# Power-5V.net
KiCad netlist of a schematic drawn in Altium Designer
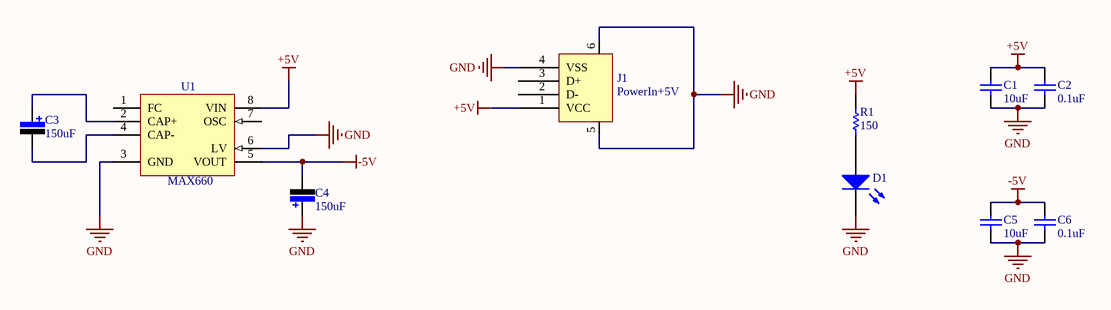
[diagram p0: Power-5V.SchDoc]

(export (version "E")
  (design (tool "Eeschema 10.0.6"))
  (components
    (comp (ref "C1")
      (value "10uF")
      (footprint "RB0.1/0.2")
      (description "无极性电容")
      (fields (field (name "Comment") "Cap") (field (name "PUBLISHER") "Altium Limited"))
      (libsource (lib "Fszhang") (part "Cap"))
    )
    (comp (ref "C2")
      (value "0.1uF")
      (footprint "C-RAD")
      (description "无极性电容")
      (fields (field (name "Comment") "Cap") (field (name "PUBLISHER") "Altium Limited"))
      (libsource (lib "Fszhang") (part "Cap"))
    )
    (comp (ref "C3")
      (value "150uF")
      (footprint "RB0.15/3")
      (description "极性电解电容")
      (fields (field (name "Comment") "Cap Pol") (field (name "PUBLISHER") "Altium Limited"))
      (libsource (lib "Fszhang") (part "Cap Pol"))
    )
    (comp (ref "C4")
      (value "150uF")
      (footprint "RB0.15/3")
      (description "极性电解电容")
      (fields (field (name "Comment") "Cap Pol") (field (name "PUBLISHER") "Altium Limited"))
      (libsource (lib "") (part "Cap Pol_1"))
    )
    (comp (ref "C5")
      (value "10uF")
      (footprint "RB0.1/0.2")
      (description "无极性电容")
      (fields (field (name "Comment") "Cap") (field (name "PUBLISHER") "Altium Limited"))
      (libsource (lib "Fszhang") (part "Cap"))
    )
    (comp (ref "C6")
      (value "0.1uF")
      (footprint "C-RAD")
      (description "无极性电容")
      (fields (field (name "Comment") "Cap") (field (name "PUBLISHER") "Altium Limited"))
      (libsource (lib "Fszhang") (part "Cap"))
    )
    (comp (ref "D1")
      (value "LED0")
      (footprint "RB2.54/4")
      (description "Typical INFRARED GaAs LED")
      (fields (field (name "PUBLISHER") "Altium Limited"))
      (libsource (lib "Miscellaneous Devices") (part "LED0"))
    )
    (comp (ref "J1")
      (value "PowerIn+5V")
      (footprint "USB_A1")
      (description "USB接口")
      (libsource (lib "Fszhang") (part "USB"))
    )
    (comp (ref "R1")
      (value "150")
      (footprint "AXIAL-0.3")
      (description "Resistor")
      (fields (field (name "Comment") "Res1") (field (name "PUBLISHER") "Altium Limited"))
      (libsource (lib "Miscellaneous Devices") (part "Res1"))
    )
    (comp (ref "U1")
      (value "MAX660")
      (footprint "DIP-8")
      (description "-5V电源芯片")
      (fields (field (name "PUBLISHER") "Altium Limited"))
      (libsource (lib "Fszhang") (part "MAX660CSA"))
    )
  )
  (nets
    (net (code "1") (name "+5V") (class "Default")
      (node (ref "C1") (pin "2") (pinfunction "2_2") (pintype "passive"))
      (node (ref "C2") (pin "2") (pinfunction "2_2") (pintype "passive"))
      (node (ref "J1") (pin "1") (pinfunction "VCC_1") (pintype "passive"))
      (node (ref "R1") (pin "2") (pinfunction "2_2") (pintype "passive"))
      (node (ref "U1") (pin "8") (pinfunction "VIN_8") (pintype "power_in"))
    )
    (net (code "2") (name "-5V") (class "Default")
      (node (ref "C4") (pin "2") (pinfunction "2_2") (pintype "passive"))
      (node (ref "C5") (pin "2") (pinfunction "2_2") (pintype "passive"))
      (node (ref "C6") (pin "2") (pinfunction "2_2") (pintype "passive"))
      (node (ref "U1") (pin "5") (pinfunction "VOUT_5") (pintype "power_in"))
    )
    (net (code "3") (name "GND") (class "Default")
      (node (ref "C1") (pin "1") (pinfunction "1_1") (pintype "passive"))
      (node (ref "C2") (pin "1") (pinfunction "1_1") (pintype "passive"))
      (node (ref "C4") (pin "1") (pinfunction "1_1") (pintype "passive"))
      (node (ref "C5") (pin "1") (pinfunction "1_1") (pintype "passive"))
      (node (ref "C6") (pin "1") (pinfunction "1_1") (pintype "passive"))
      (node (ref "D1") (pin "2") (pinfunction "K_2") (pintype "passive"))
      (node (ref "J1") (pin "4") (pinfunction "VSS_4") (pintype "passive"))
      (node (ref "J1") (pin "5") (pinfunction "5_5") (pintype "passive"))
      (node (ref "J1") (pin "6") (pinfunction "6_6") (pintype "passive"))
      (node (ref "U1") (pin "3") (pinfunction "GND_3") (pintype "power_in"))
      (node (ref "U1") (pin "6") (pinfunction "LV_6") (pintype "input"))
    )
    (net (code "4") (name "Net-(D1-A)") (class "Default")
      (node (ref "D1") (pin "1") (pinfunction "A_1") (pintype "passive"))
      (node (ref "R1") (pin "1") (pinfunction "1_1") (pintype "passive"))
    )
    (net (code "5") (name "Net-(U1-CAP+)") (class "Default")
      (node (ref "C3") (pin "1") (pinfunction "1_1") (pintype "passive"))
      (node (ref "U1") (pin "2") (pinfunction "CAP+_2") (pintype "passive"))
    )
    (net (code "6") (name "Net-(U1-CAP-)") (class "Default")
      (node (ref "C3") (pin "2") (pinfunction "2_2") (pintype "passive"))
      (node (ref "U1") (pin "4") (pinfunction "CAP-_4") (pintype "passive"))
    )
    (net (code "7") (name "unconnected-(J1-D+-Pad3)") (class "Default")
      (node (ref "J1") (pin "3") (pinfunction "D+_3") (pintype "passive"))
    )
    (net (code "8") (name "unconnected-(J1-D--Pad2)") (class "Default")
      (node (ref "J1") (pin "2") (pinfunction "D-_2") (pintype "passive"))
    )
    (net (code "9") (name "unconnected-(U1-FC-Pad1)") (class "Default")
      (node (ref "U1") (pin "1") (pinfunction "FC_1") (pintype "passive"))
    )
    (net (code "10") (name "unconnected-(U1-OSC-Pad7)") (class "Default")
      (node (ref "U1") (pin "7") (pinfunction "OSC_7") (pintype "input"))
    )
  )
)
